# PIN_Gamma_Power.net
KiCad netlist of a schematic drawn in Altium Designer
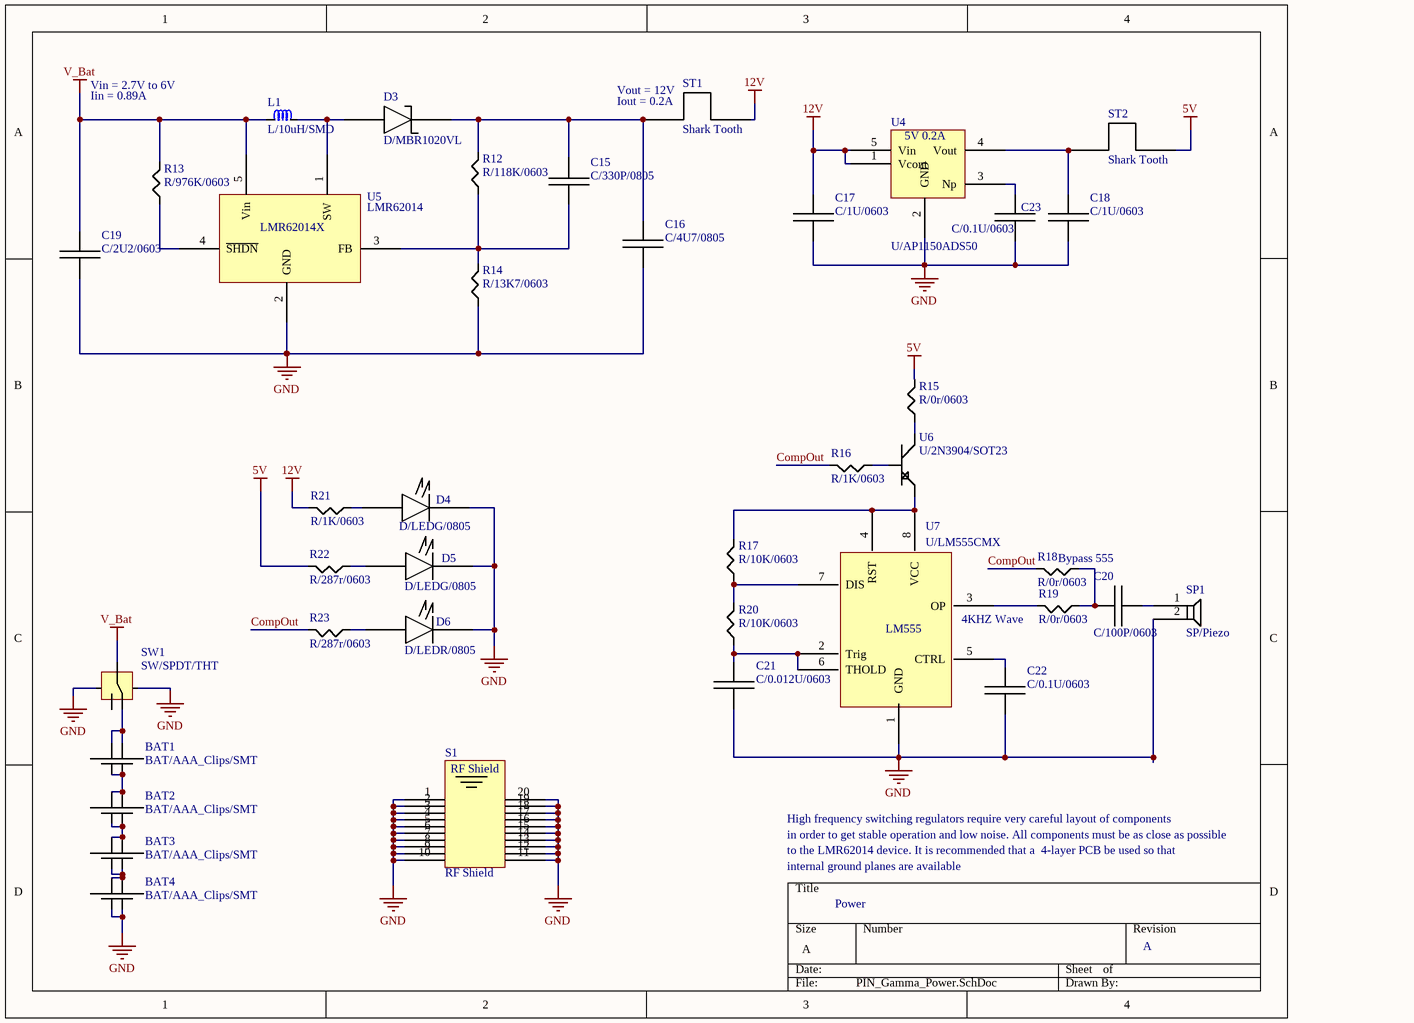
[diagram p0: PIN_Gamma_Power.SchDoc]

(export (version "E")
  (design (tool "Eeschema 10.0.6"))
  (components
    (comp (ref "BAT1")
      (value "BAT/AAA_Clips/SMT")
      (footprint "AAA_Battery_SMT")
      (description "AAA 1.5V SMT Clips")
      (fields (field (name "DIGIKEY PART") "36-55-ND"))
      (libsource (lib "Kyle_Integrated_Library") (part "BAT/AAA_Clips/SMT"))
    )
    (comp (ref "BAT2")
      (value "BAT/AAA_Clips/SMT")
      (footprint "AAA_Battery_SMT")
      (description "AAA 1.5V SMT Clips")
      (fields (field (name "DIGIKEY PART") "36-55-ND"))
      (libsource (lib "Kyle_Integrated_Library") (part "BAT/AAA_Clips/SMT"))
    )
    (comp (ref "BAT3")
      (value "BAT/AAA_Clips/SMT")
      (footprint "AAA_Battery_SMT")
      (description "AAA 1.5V SMT Clips")
      (fields (field (name "DIGIKEY PART") "36-55-ND"))
      (libsource (lib "Kyle_Integrated_Library") (part "BAT/AAA_Clips/SMT"))
    )
    (comp (ref "BAT4")
      (value "BAT/AAA_Clips/SMT")
      (footprint "AAA_Battery_SMT")
      (description "AAA 1.5V SMT Clips")
      (fields (field (name "DIGIKEY PART") "36-55-ND"))
      (libsource (lib "Kyle_Integrated_Library") (part "BAT/AAA_Clips/SMT"))
    )
    (comp (ref "C15")
      (value "C/330P/0805")
      (footprint "C/0603")
      (description "CAP CER 330PF 50V C0G/NP0 0805")
      (libsource (lib "Kyle_Integrated_Library") (part "C/330P/0805"))
    )
    (comp (ref "C16")
      (value "C/4U7/0805")
      (footprint "R/0805")
      (description "CAP CER 4.7UF 50V X5R 0805")
      (libsource (lib "Kyle_Integrated_Library") (part "C/4U7/0805"))
    )
    (comp (ref "C17")
      (value "C/1U/0603")
      (footprint "C/0603")
      (description "CAP CER 1UF 50V X5R 0603")
      (libsource (lib "Kyle_Integrated_Library") (part "C/1U/0603"))
    )
    (comp (ref "C18")
      (value "C/1U/0603")
      (footprint "C/0603")
      (description "CAP CER 1UF 50V X5R 0603")
      (libsource (lib "Kyle_Integrated_Library") (part "C/1U/0603"))
    )
    (comp (ref "C19")
      (value "C/2U2/0603")
      (footprint "C/0603")
      (description "2.2µF ±10% 10V Ceramic Capacitor X5R 0603 (1608 Metric)")
      (libsource (lib "Kyle_Integrated_Library") (part "C/2U2/0603"))
    )
    (comp (ref "C20")
      (value "C/100P/0603")
      (footprint "C/0603")
      (description "CAP CER 100PF 50V C0G/NP0 0603")
      (libsource (lib "Kyle_Integrated_Library") (part "C/100P/0603"))
    )
    (comp (ref "C21")
      (value "C/0.012U/0603")
      (footprint "C/0603")
      (description "CAP CER 0.012UF 50V X7R 0603")
      (fields (field (name "DIGIKEY PART") "1276-1785-1-ND"))
      (libsource (lib "Kyle_Integrated_Library") (part "C/0.012U/0603"))
    )
    (comp (ref "C22")
      (value "C/0.1U/0603")
      (footprint "C/0603")
      (description "CAP CER 0.1UF 50V X7R 0603")
      (fields (field (name "DIGIKEY PART") "399-7845-1-ND"))
      (libsource (lib "Kyle_Integrated_Library") (part "C/0.1U/0603"))
    )
    (comp (ref "C23")
      (value "C/0.1U/0603")
      (footprint "C/0603")
      (description "CAP CER 0.1UF 50V X7R 0603")
      (fields (field (name "DIGIKEY PART") "399-7845-1-ND"))
      (libsource (lib "Kyle_Integrated_Library") (part "C/0.1U/0603"))
    )
    (comp (ref "D3")
      (value "D/MBR1020VL")
      (footprint "SOD-123F")
      (description "Diode Schottky 20V 1A Surface Mount SOD-123F")
      (fields (field (name "DIGIKEY PART") "MBR1020VLCT-ND"))
      (libsource (lib "Kyle_Integrated_Library") (part "D/MBR1020VL"))
    )
    (comp (ref "D4")
      (value "D/LEDG/0805")
      (footprint "D/0805")
      (description "LED GREEN CLEAR 2.1V 0805 SMD")
      (fields (field (name "DIGIKEY PART") "160-1423-1-ND"))
      (libsource (lib "Kyle_Integrated_Library") (part "D/LEDG/0805"))
    )
    (comp (ref "D5")
      (value "D/LEDG/0805")
      (footprint "D/0805")
      (description "LED GREEN CLEAR 2.1V 0805 SMD")
      (fields (field (name "DIGIKEY PART") "160-1423-1-ND"))
      (libsource (lib "Kyle_Integrated_Library") (part "D/LEDG/0805"))
    )
    (comp (ref "D6")
      (value "D/LEDR/0805")
      (footprint "D/0805")
      (description "LED GREEN CLEAR 2V 0805 SMD")
      (fields (field (name "DIGIKEY PART") "160-1427-1-ND"))
      (libsource (lib "Kyle_Integrated_Library") (part "D/LEDR/0805"))
    )
    (comp (ref "L1")
      (value "L/10uH/SMD")
      (footprint "INDP3030X15N")
      (description "10µH Semi-Shielded Wirewound Inductor 1A 276 mOhm Max Nonstandard")
      (fields (field (name "DIGIKEY PART") "SRN3015-100MCT-ND"))
      (libsource (lib "Kyle_Integrated_Library") (part "L/10uH/SMD"))
    )
    (comp (ref "R12")
      (value "R/118K/0603")
      (footprint "R/0603")
      (description "RES SMD 118K OHM 1% 1/10W 0603")
      (fields (field (name "DIGIKEY PART") "311-118KHRCT-ND"))
      (libsource (lib "Kyle_Integrated_Library") (part "R/118K/0603"))
    )
    (comp (ref "R13")
      (value "R/976K/0603")
      (footprint "R/0603")
      (description "RES SMD 976K OHM 1% 1/10W 0603")
      (fields (field (name "DIGIKEY PART") "311-976KHRCT-ND"))
      (libsource (lib "Kyle_Integrated_Library") (part "R/976K/0603"))
    )
    (comp (ref "R14")
      (value "R/13K7/0603")
      (footprint "R/0603")
      (description "RES SMD 13.7K OHM 1% 1/10W 0603")
      (fields (field (name "DIGIKEY PART") "311-13.7KHRCT-ND"))
      (libsource (lib "Kyle_Integrated_Library") (part "R/13K7/0603"))
    )
    (comp (ref "R15")
      (value "R/0r/0603")
      (footprint "R/0603")
      (description "RES SMD 0 OHM JUMPER 1/10W 0603")
      (fields (field (name "DIGIKEY PART") "311-0.0GRCT-ND"))
      (libsource (lib "Kyle_Integrated_Library") (part "R/0r/0603"))
    )
    (comp (ref "R16")
      (value "R/1K/0603")
      (footprint "R/0603")
      (description "RES SMD 1K OHM 5% 1/10W 0603")
      (fields (field (name "DIGIKEY PART") "311-1.0KGRCT-ND"))
      (libsource (lib "Kyle_Sch_Lib") (part "R/1K/0603"))
    )
    (comp (ref "R17")
      (value "R/10K/0603")
      (footprint "R/0603")
      (description "RES SMD 10K OHM 5% 1/10W 0603")
      (fields (field (name "DIGIKEY PART") "311-10KGRCT-ND"))
      (libsource (lib "Kyle_Integrated_Library") (part "R/10K/0603"))
    )
    (comp (ref "R18")
      (value "R/0r/0603")
      (footprint "R/0603")
      (description "RES SMD 0 OHM JUMPER 1/10W 0603")
      (fields (field (name "DIGIKEY PART") "311-0.0GRCT-ND"))
      (libsource (lib "Kyle_Integrated_Library") (part "R/0r/0603"))
    )
    (comp (ref "R19")
      (value "R/0r/0603")
      (footprint "R/0603")
      (description "RES SMD 0 OHM JUMPER 1/10W 0603")
      (fields (field (name "DIGIKEY PART") "311-0.0GRCT-ND"))
      (libsource (lib "Kyle_Integrated_Library") (part "R/0r/0603"))
    )
    (comp (ref "R20")
      (value "R/10K/0603")
      (footprint "R/0603")
      (description "RES SMD 10K OHM 5% 1/10W 0603")
      (fields (field (name "DIGIKEY PART") "311-10KGRCT-ND"))
      (libsource (lib "Kyle_Integrated_Library") (part "R/10K/0603"))
    )
    (comp (ref "R21")
      (value "R/1K/0603")
      (footprint "R/0603")
      (description "RES SMD 1K OHM 5% 1/10W 0603")
      (fields (field (name "DIGIKEY PART") "311-1.0KGRCT-ND"))
      (libsource (lib "Kyle_Integrated_Library") (part "R/1K/0603"))
    )
    (comp (ref "R22")
      (value "R/287r/0603")
      (footprint "R/0603")
      (description "RES SMD 287 OHM 1% 1/10W 0603")
      (fields (field (name "DIGIKEY PART") "311-287HRCT-ND"))
      (libsource (lib "Kyle_Integrated_Library") (part "R/287r/0603"))
    )
    (comp (ref "R23")
      (value "R/287r/0603")
      (footprint "R/0603")
      (description "RES SMD 287 OHM 1% 1/10W 0603")
      (fields (field (name "DIGIKEY PART") "311-287HRCT-ND"))
      (libsource (lib "Kyle_Integrated_Library") (part "R/287r/0603"))
    )
    (comp (ref "S1")
      (value "RF Shield")
      (footprint "RF Shield")
      (description "SMS-403C & SMS-403F RF Shield Cover 1.058\" (26.87mm) X 1.058\" (26.87mm) Non-Vented Surface Mount")
      (libsource (lib "Kyle_Sch_Lib") (part "RF Shield"))
    )
    (comp (ref "SP1")
      (value "SP/Piezo")
      (footprint "AUDIO PIEZO")
      (description "AUDIO PIEZO TRANSDUCER Max 12.5V 4KHZ SMD")
      (fields (field (name "DIGIKEY PART") "490-9647-1-ND"))
      (libsource (lib "Kyle_Integrated_Library") (part "SP/Piezo"))
    )
    (comp (ref "ST1")
      (value "Shark Tooth")
      (footprint "SharkTooth")
      (description "Sharks Tooth Small")
      (libsource (lib "SC_Library") (part "Shark Tooth"))
    )
    (comp (ref "ST2")
      (value "Shark Tooth")
      (footprint "SharkTooth")
      (description "Sharks Tooth Small")
      (libsource (lib "SC_Library") (part "Shark Tooth"))
    )
    (comp (ref "SW1")
      (value "SW/SPDT/THT")
      (footprint "SW/SPDT/THT")
      (description "SWITCH SLIDE SPDT 200MA 30V")
      (fields (field (name "DIGIKEY PART") "A107673-ND"))
      (libsource (lib "Kyle_Integrated_Library") (part "SW/SPDT/THT"))
    )
    (comp (ref "U4")
      (value "U/AP1150ADS50")
      (footprint "SOT23-5")
      (description "IC REG LINEAR 5V 200MA SOT23-5")
      (fields (field (name "DIGIKEY PART") "AP1150ADS50CT-ND"))
      (libsource (lib "Kyle_Integrated_Library") (part "U/AP1150ADS50"))
    )
    (comp (ref "U5")
      (value "LMR62014")
      (footprint "SOT23-5")
      (description "Boost Switching Regulator IC Positive Adjustable 3V 1 Output 1.8A (Switch) SC-74A, SOT-753")
      (libsource (lib "Kyle_Integrated_Library") (part "U/LMR62014XMF/NOPBCT-ND"))
    )
    (comp (ref "U6")
      (value "U/2N3904/SOT23")
      (footprint "SOT23-3")
      (description "TRANS NPN 40V 0.2A SOT23")
      (fields (field (name "DIGIKEY PART") "MMBT3904LT3GOSCT-ND"))
      (libsource (lib "Kyle_Integrated_Library") (part "U/2N3904/SOT23"))
    )
    (comp (ref "U7")
      (value "U/LM555CMX")
      (footprint "SO8")
      (description "555 Type, Timer/Oscillator (Single) IC 8-SOIC")
      (libsource (lib "Kyle_Sch_Lib") (part "U/LM555CMX"))
    )
  )
  (nets
    (net (code "1") (name "/CompOut") (class "Default")
      (node (ref "R16") (pin "1") (pinfunction "1_1") (pintype "passive"))
      (node (ref "R18") (pin "1") (pinfunction "1_1") (pintype "passive"))
      (node (ref "R23") (pin "1") (pinfunction "1_1") (pintype "passive"))
    )
    (net (code "2") (name "5V") (class "Default")
      (node (ref "R15") (pin "1") (pinfunction "1_1") (pintype "passive"))
      (node (ref "R22") (pin "1") (pinfunction "1_1") (pintype "passive"))
      (node (ref "ST2") (pin "2") (pinfunction "2_2") (pintype "power_in"))
    )
    (net (code "3") (name "12V") (class "Default")
      (node (ref "C17") (pin "1") (pinfunction "1_1") (pintype "passive"))
      (node (ref "R21") (pin "1") (pinfunction "1_1") (pintype "passive"))
      (node (ref "ST1") (pin "2") (pinfunction "2_2") (pintype "power_in"))
      (node (ref "U4") (pin "1") (pinfunction "Vcont_1") (pintype "passive"))
      (node (ref "U4") (pin "5") (pinfunction "Vin_5") (pintype "power_in"))
    )
    (net (code "4") (name "GND") (class "Default")
      (node (ref "BAT4") (pin "3") (pinfunction "3_3") (pintype "power_in"))
      (node (ref "BAT4") (pin "4") (pinfunction "4_4") (pintype "passive"))
      (node (ref "C16") (pin "2") (pinfunction "2_2") (pintype "passive"))
      (node (ref "C17") (pin "2") (pinfunction "2_2") (pintype "passive"))
      (node (ref "C18") (pin "2") (pinfunction "2_2") (pintype "passive"))
      (node (ref "C19") (pin "2") (pinfunction "2_2") (pintype "passive"))
      (node (ref "C21") (pin "2") (pinfunction "2_2") (pintype "passive"))
      (node (ref "C22") (pin "2") (pinfunction "2_2") (pintype "passive"))
      (node (ref "C23") (pin "2") (pinfunction "2_2") (pintype "passive"))
      (node (ref "D4") (pin "1") (pinfunction "1_1") (pintype "passive"))
      (node (ref "D5") (pin "1") (pinfunction "1_1") (pintype "passive"))
      (node (ref "D6") (pin "1") (pinfunction "1_1") (pintype "passive"))
      (node (ref "R14") (pin "2") (pinfunction "2_2") (pintype "passive"))
      (node (ref "S1") (pin "1") (pinfunction "GND1_1") (pintype "passive"))
      (node (ref "S1") (pin "10") (pinfunction "GND10_10") (pintype "passive"))
      (node (ref "S1") (pin "11") (pinfunction "GND11_11") (pintype "passive"))
      (node (ref "S1") (pin "12") (pinfunction "GND12_12") (pintype "passive"))
      (node (ref "S1") (pin "13") (pinfunction "GND13_13") (pintype "passive"))
      (node (ref "S1") (pin "14") (pinfunction "GND14_14") (pintype "passive"))
      (node (ref "S1") (pin "15") (pinfunction "GND15_15") (pintype "passive"))
      (node (ref "S1") (pin "16") (pinfunction "GND16_16") (pintype "passive"))
      (node (ref "S1") (pin "17") (pinfunction "GND17_17") (pintype "passive"))
      (node (ref "S1") (pin "18") (pinfunction "GND18_18") (pintype "passive"))
      (node (ref "S1") (pin "19") (pinfunction "GND19_19") (pintype "passive"))
      (node (ref "S1") (pin "2") (pinfunction "GND2_2") (pintype "passive"))
      (node (ref "S1") (pin "20") (pinfunction "GND20_20") (pintype "passive"))
      (node (ref "S1") (pin "3") (pinfunction "GND3_3") (pintype "passive"))
      (node (ref "S1") (pin "4") (pinfunction "GND4_4") (pintype "passive"))
      (node (ref "S1") (pin "5") (pinfunction "GND5_5") (pintype "passive"))
      (node (ref "S1") (pin "6") (pinfunction "GND6_6") (pintype "passive"))
      (node (ref "S1") (pin "7") (pinfunction "GND7_7") (pintype "passive"))
      (node (ref "S1") (pin "8") (pinfunction "GND8_8") (pintype "passive"))
      (node (ref "S1") (pin "9") (pinfunction "GND9_9") (pintype "passive"))
      (node (ref "SP1") (pin "2") (pinfunction "2_2") (pintype "passive"))
      (node (ref "SW1") (pin "1") (pinfunction "GND_1") (pintype "power_in"))
      (node (ref "SW1") (pin "5") (pinfunction "GND_5") (pintype "power_in"))
      (node (ref "U4") (pin "2") (pinfunction "GND_2") (pintype "power_in"))
      (node (ref "U5") (pin "2") (pinfunction "GND_2") (pintype "passive"))
      (node (ref "U7") (pin "1") (pinfunction "GND_1") (pintype "power_in"))
    )
    (net (code "5") (name "Net-(BAT1-Pad3)") (class "Default")
      (node (ref "BAT1") (pin "3") (pinfunction "3_3") (pintype "power_in"))
      (node (ref "BAT1") (pin "4") (pinfunction "4_4") (pintype "passive"))
      (node (ref "BAT2") (pin "1") (pinfunction "1_1") (pintype "power_in"))
      (node (ref "BAT2") (pin "2") (pinfunction "2_2") (pintype "power_in"))
    )
    (net (code "6") (name "Net-(BAT2-Pad3)") (class "Default")
      (node (ref "BAT2") (pin "3") (pinfunction "3_3") (pintype "power_in"))
      (node (ref "BAT2") (pin "4") (pinfunction "4_4") (pintype "passive"))
      (node (ref "BAT3") (pin "1") (pinfunction "1_1") (pintype "power_in"))
      (node (ref "BAT3") (pin "2") (pinfunction "2_2") (pintype "power_in"))
    )
    (net (code "7") (name "Net-(BAT3-Pad3)") (class "Default")
      (node (ref "BAT3") (pin "3") (pinfunction "3_3") (pintype "power_in"))
      (node (ref "BAT3") (pin "4") (pinfunction "4_4") (pintype "passive"))
      (node (ref "BAT4") (pin "1") (pinfunction "1_1") (pintype "power_in"))
      (node (ref "BAT4") (pin "2") (pinfunction "2_2") (pintype "power_in"))
    )
    (net (code "8") (name "Net-(C15-Pad2)") (class "Default")
      (node (ref "C15") (pin "2") (pinfunction "2_2") (pintype "passive"))
      (node (ref "C16") (pin "1") (pinfunction "1_1") (pintype "passive"))
      (node (ref "D3") (pin "1") (pinfunction "1_1") (pintype "passive"))
      (node (ref "R12") (pin "1") (pinfunction "1_1") (pintype "passive"))
      (node (ref "ST1") (pin "1") (pinfunction "1_1") (pintype "power_in"))
    )
    (net (code "9") (name "Net-(C20-Pad1)") (class "Default")
      (node (ref "C20") (pin "1") (pinfunction "1_1") (pintype "passive"))
      (node (ref "R18") (pin "2") (pinfunction "2_2") (pintype "passive"))
      (node (ref "R19") (pin "2") (pinfunction "2_2") (pintype "passive"))
    )
    (net (code "10") (name "Net-(C20-Pad2)") (class "Default")
      (node (ref "C20") (pin "2") (pinfunction "2_2") (pintype "passive"))
      (node (ref "SP1") (pin "1") (pinfunction "1_1") (pintype "passive"))
    )
    (net (code "11") (name "Net-(D4-Pad2)") (class "Default")
      (node (ref "D4") (pin "2") (pinfunction "2_2") (pintype "passive"))
      (node (ref "R21") (pin "2") (pinfunction "2_2") (pintype "passive"))
    )
    (net (code "12") (name "Net-(D5-Pad2)") (class "Default")
      (node (ref "D5") (pin "2") (pinfunction "2_2") (pintype "passive"))
      (node (ref "R22") (pin "2") (pinfunction "2_2") (pintype "passive"))
    )
    (net (code "13") (name "Net-(D6-Pad2)") (class "Default")
      (node (ref "D6") (pin "2") (pinfunction "2_2") (pintype "passive"))
      (node (ref "R23") (pin "2") (pinfunction "2_2") (pintype "passive"))
    )
    (net (code "14") (name "Net-(SW1-B)") (class "Default")
      (node (ref "BAT1") (pin "1") (pinfunction "1_1") (pintype "power_in"))
      (node (ref "BAT1") (pin "2") (pinfunction "2_2") (pintype "power_in"))
      (node (ref "SW1") (pin "4") (pinfunction "B_4") (pintype "power_in"))
    )
    (net (code "15") (name "Net-(U4-Np)") (class "Default")
      (node (ref "C23") (pin "1") (pinfunction "1_1") (pintype "passive"))
      (node (ref "U4") (pin "3") (pinfunction "Np_3") (pintype "passive"))
    )
    (net (code "16") (name "Net-(U4-Vout)") (class "Default")
      (node (ref "C18") (pin "1") (pinfunction "1_1") (pintype "passive"))
      (node (ref "ST2") (pin "1") (pinfunction "1_1") (pintype "power_in"))
      (node (ref "U4") (pin "4") (pinfunction "Vout_4") (pintype "power_in"))
    )
    (net (code "17") (name "Net-(U5-FB)") (class "Default")
      (node (ref "C15") (pin "1") (pinfunction "1_1") (pintype "passive"))
      (node (ref "R12") (pin "2") (pinfunction "2_2") (pintype "passive"))
      (node (ref "R14") (pin "1") (pinfunction "1_1") (pintype "passive"))
      (node (ref "U5") (pin "3") (pinfunction "FB_3") (pintype "passive"))
    )
    (net (code "18") (name "Net-(U5-SW)") (class "Default")
      (node (ref "D3") (pin "2") (pinfunction "2_2") (pintype "passive"))
      (node (ref "L1") (pin "1") (pinfunction "1_1") (pintype "passive"))
      (node (ref "U5") (pin "1") (pinfunction "SW_1") (pintype "passive"))
    )
    (net (code "19") (name "Net-(U5-~{SHDN})") (class "Default")
      (node (ref "R13") (pin "2") (pinfunction "2_2") (pintype "passive"))
      (node (ref "U5") (pin "4") (pinfunction "~{SHDN}_4") (pintype "passive"))
    )
    (net (code "20") (name "Net-(U6-Base)") (class "Default")
      (node (ref "R16") (pin "2") (pinfunction "2_2") (pintype "passive"))
      (node (ref "U6") (pin "1") (pinfunction "Base_1") (pintype "passive"))
    )
    (net (code "21") (name "Net-(U6-Collector)") (class "Default")
      (node (ref "R15") (pin "2") (pinfunction "2_2") (pintype "passive"))
      (node (ref "U6") (pin "3") (pinfunction "Collector_3") (pintype "passive"))
    )
    (net (code "22") (name "Net-(U6-Emitter)") (class "Default")
      (node (ref "R17") (pin "1") (pinfunction "1_1") (pintype "passive"))
      (node (ref "U6") (pin "2") (pinfunction "Emitter_2") (pintype "passive"))
      (node (ref "U7") (pin "4") (pinfunction "RST_4") (pintype "passive"))
      (node (ref "U7") (pin "8") (pinfunction "VCC_8") (pintype "power_in"))
    )
    (net (code "23") (name "Net-(U7-CTRL)") (class "Default")
      (node (ref "C22") (pin "1") (pinfunction "1_1") (pintype "passive"))
      (node (ref "U7") (pin "5") (pinfunction "CTRL_5") (pintype "passive"))
    )
    (net (code "24") (name "Net-(U7-DIS)") (class "Default")
      (node (ref "R17") (pin "2") (pinfunction "2_2") (pintype "passive"))
      (node (ref "R20") (pin "1") (pinfunction "1_1") (pintype "passive"))
      (node (ref "U7") (pin "7") (pinfunction "DIS_7") (pintype "passive"))
    )
    (net (code "25") (name "Net-(U7-OP)") (class "Default")
      (node (ref "R19") (pin "1") (pinfunction "1_1") (pintype "passive"))
      (node (ref "U7") (pin "3") (pinfunction "OP_3") (pintype "passive"))
    )
    (net (code "26") (name "Net-(U7-THOLD)") (class "Default")
      (node (ref "C21") (pin "1") (pinfunction "1_1") (pintype "passive"))
      (node (ref "R20") (pin "2") (pinfunction "2_2") (pintype "passive"))
      (node (ref "U7") (pin "2") (pinfunction "Trig_2") (pintype "passive"))
      (node (ref "U7") (pin "6") (pinfunction "THOLD_6") (pintype "passive"))
    )
    (net (code "27") (name "V_Bat") (class "Default")
      (node (ref "C19") (pin "1") (pinfunction "1_1") (pintype "passive"))
      (node (ref "L1") (pin "2") (pinfunction "2_2") (pintype "passive"))
      (node (ref "R13") (pin "1") (pinfunction "1_1") (pintype "passive"))
      (node (ref "SW1") (pin "3") (pinfunction "COM_3") (pintype "power_in"))
      (node (ref "U5") (pin "5") (pinfunction "Vin_5") (pintype "passive"))
    )
    (net (code "28") (name "unconnected-(SW1-A-Pad2)") (class "Default")
      (node (ref "SW1") (pin "2") (pinfunction "A_2") (pintype "power_in"))
    )
  )
)
